# usb_power.net
KiCad netlist of a schematic drawn in EAGLE
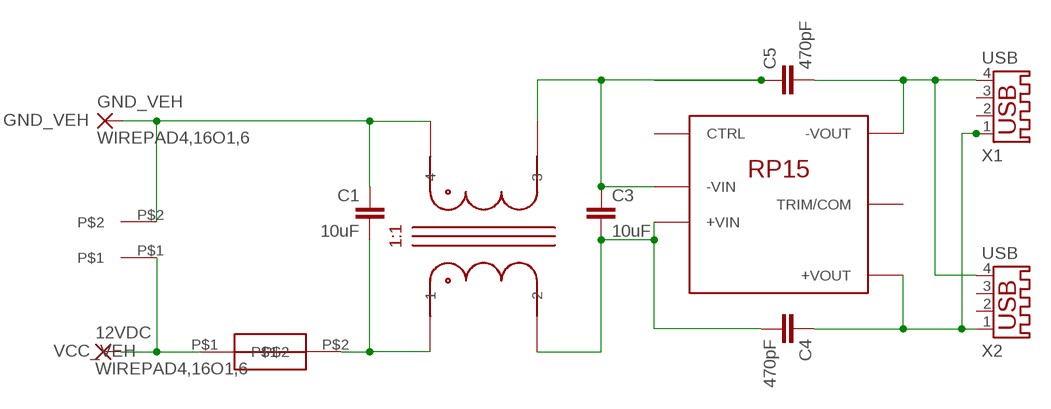
[diagram p0: schematic, sheet 1]

(export (version "E")
  (design (tool "Eeschema 10.0.6"))
  (components
    (comp (ref "12VDC")
      (value "WIREPAD4,16O1,6")
      (footprint "eagle-import:4,16O1,6")
      (libsource (lib "eagle-import") (part "WIREPAD4,16O1,6"))
    )
    (comp (ref "C1")
      (value "10uF")
      (footprint "eagle-import:C1812")
      (libsource (lib "eagle-import") (part "C-EUC1812"))
    )
    (comp (ref "C3")
      (value "10uF")
      (footprint "eagle-import:C1812")
      (libsource (lib "eagle-import") (part "C-EUC1812"))
    )
    (comp (ref "C4")
      (value "470pF")
      (footprint "eagle-import:C1808")
      (libsource (lib "eagle-import") (part "C-EUC1808"))
    )
    (comp (ref "C5")
      (value "470pF")
      (footprint "eagle-import:C1808")
      (libsource (lib "eagle-import") (part "C-EUC1808"))
    )
    (comp (ref "GND_VEH")
      (value "WIREPAD4,16O1,6")
      (footprint "eagle-import:4,16O1,6")
      (libsource (lib "eagle-import") (part "WIREPAD4,16O1,6"))
    )
    (comp (ref "RECOM")
      (value "RP15-1205SA")
      (footprint "eagle-import:RP15")
      (libsource (lib "eagle-import") (part "RP15-1205SA"))
    )
    (comp (ref "U$2")
      (value "1.6A")
      (footprint "eagle-import:C1608")
      (libsource (lib "eagle-import") (part "FUSE"))
    )
    (comp (ref "U$3")
      (value "COMMON-MODE-CHOKE")
      (footprint "eagle-import:CMS2")
      (libsource (lib "eagle-import") (part "COMMON-MODE-CHOKE"))
    )
    (comp (ref "U$4")
      (value "POWERPOLE_RIGHT")
      (footprint "eagle-import:1336G1")
      (libsource (lib "eagle-import") (part "POWERPOLE_RIGHT"))
    )
    (comp (ref "X1")
      (value "USB")
      (footprint "eagle-import:USB-A003")
      (libsource (lib "eagle-import") (part "USB-A003"))
    )
    (comp (ref "X2")
      (value "USB")
      (footprint "eagle-import:USB-A003")
      (libsource (lib "eagle-import") (part "USB-A003"))
    )
  )
  (nets
    (net (code "1") (name "/GND_VEH") (class "Default")
      (node (ref "C1") (pin "1") (pinfunction "1_1") (pintype "passive"))
      (node (ref "GND_VEH") (pin "1") (pinfunction "P_1") (pintype "passive"))
      (node (ref "U$3") (pin "4") (pinfunction "4_4") (pintype "bidirectional"))
      (node (ref "U$4") (pin "P$2") (pinfunction "P$2_P$2") (pintype "bidirectional"))
    )
    (net (code "2") (name "/VCC_VEH") (class "Default")
      (node (ref "12VDC") (pin "1") (pinfunction "P_1") (pintype "passive"))
      (node (ref "U$2") (pin "P$1") (pinfunction "P$1_P$1") (pintype "bidirectional"))
      (node (ref "U$4") (pin "P$1") (pinfunction "P$1_P$1") (pintype "bidirectional"))
    )
    (net (code "3") (name "Net-(C1-Pad2)") (class "Default")
      (node (ref "C1") (pin "2") (pinfunction "2_2") (pintype "passive"))
      (node (ref "U$2") (pin "P$2") (pinfunction "P$2_P$2") (pintype "bidirectional"))
      (node (ref "U$3") (pin "1") (pinfunction "1_1") (pintype "bidirectional"))
    )
    (net (code "4") (name "Net-(C3-Pad1)") (class "Default")
      (node (ref "C3") (pin "1") (pinfunction "1_1") (pintype "passive"))
      (node (ref "C5") (pin "1") (pinfunction "1_1") (pintype "passive"))
      (node (ref "RECOM") (pin "-VIN") (pinfunction "-VIN_-VIN") (pintype "bidirectional"))
      (node (ref "U$3") (pin "3") (pinfunction "3_3") (pintype "bidirectional"))
    )
    (net (code "5") (name "Net-(C3-Pad2)") (class "Default")
      (node (ref "C3") (pin "2") (pinfunction "2_2") (pintype "passive"))
      (node (ref "C4") (pin "2") (pinfunction "2_2") (pintype "passive"))
      (node (ref "RECOM") (pin "+VIN") (pinfunction "+VIN_+VIN") (pintype "bidirectional"))
      (node (ref "U$3") (pin "2") (pinfunction "2_2") (pintype "bidirectional"))
    )
    (net (code "6") (name "Net-(C4-Pad1)") (class "Default")
      (node (ref "C4") (pin "1") (pinfunction "1_1") (pintype "passive"))
      (node (ref "RECOM") (pin "+VOUT") (pinfunction "+VOUT_+VOUT") (pintype "bidirectional"))
      (node (ref "X1") (pin "1") (pinfunction "1_1") (pintype "passive"))
      (node (ref "X2") (pin "1") (pinfunction "1_1") (pintype "passive"))
    )
    (net (code "7") (name "Net-(C5-Pad2)") (class "Default")
      (node (ref "C5") (pin "2") (pinfunction "2_2") (pintype "passive"))
      (node (ref "RECOM") (pin "-VOUT") (pinfunction "-VOUT_-VOUT") (pintype "bidirectional"))
      (node (ref "X1") (pin "4") (pinfunction "4_4") (pintype "passive"))
      (node (ref "X2") (pin "4") (pinfunction "4_4") (pintype "passive"))
    )
    (net (code "8") (name "unconnected-(RECOM-PadCTRL)") (class "Default")
      (node (ref "RECOM") (pin "CTRL") (pinfunction "CTRL_CTRL") (pintype "bidirectional"))
    )
    (net (code "9") (name "unconnected-(RECOM-PadTRIM{slash}COM)") (class "Default")
      (node (ref "RECOM") (pin "TRIM/COM") (pinfunction "TRIM/COM_TRIM/COM") (pintype "bidirectional"))
    )
    (net (code "10") (name "unconnected-(X1-Pad2)") (class "Default")
      (node (ref "X1") (pin "2") (pinfunction "2_2") (pintype "passive"))
    )
    (net (code "11") (name "unconnected-(X1-Pad3)") (class "Default")
      (node (ref "X1") (pin "3") (pinfunction "3_3") (pintype "passive"))
    )
    (net (code "12") (name "unconnected-(X2-Pad2)") (class "Default")
      (node (ref "X2") (pin "2") (pinfunction "2_2") (pintype "passive"))
    )
    (net (code "13") (name "unconnected-(X2-Pad3)") (class "Default")
      (node (ref "X2") (pin "3") (pinfunction "3_3") (pintype "passive"))
    )
  )
)
